# Protection_Circuit_12V.net
KiCad netlist of a schematic drawn in Altium Designer
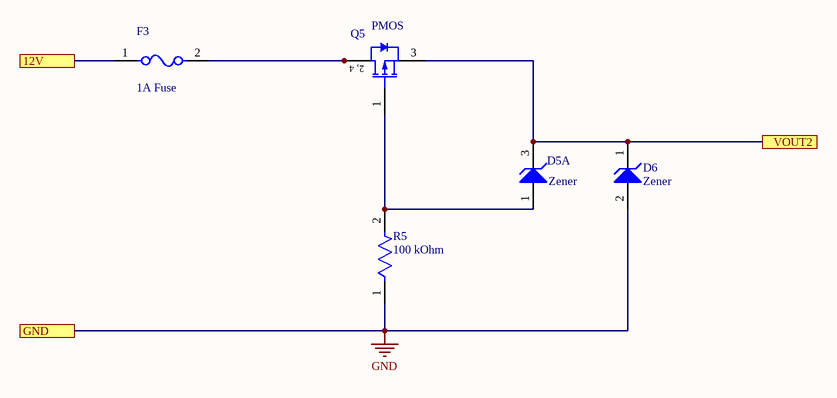
[diagram p0: Protection Circuit 12V.SchDoc]

(export (version "E")
  (design (tool "Eeschema 10.0.6"))
  (components
    (comp (ref "D5")
      (value "Zener")
      (footprint "ONSC-SOT-23-3-318-08_V")
      (description "Zener Voltage Regulator, 225 mW, 3-Pin SOT-23, Pb-Free, Tape and Reel")
      (fields (field (name "PARTNUMBER") "MMBZ5245BLT3G") (field (name "MANUFACTURER") "On Semiconductor"))
      (libsource (lib "Altium Content Vault") (part "ONSC-A1K3-3"))
    )
    (comp (ref "D6")
      (value "Zener")
      (footprint "ONSC-SMB-2-403A-03_H_V")
      (description "3 W Zener Voltage Regulator, 2-Pin SMB, Pb-Free, Tape and Reel")
      (fields (field (name "MANUFACTURER") "On Semiconductor") (field (name "PARTNUMBER") "1SMB5927BT3G"))
      (libsource (lib "Altium Content Vault") (part "ONSC-K1A2-2"))
    )
    (comp (ref "F3")
      (value "1A Fuse")
      (footprint "FP-0603SFS-MFG")
      (description "FUSE BOARD MOUNT 1A 32VDC 0603")
      (fields
        (field (name "OCTOPART") "https://octopart.com/0603sfs100f%2F32-2-littelfuse-74214378")
        (field (name "MANUFACTURER PART NUMBER") "0603SFS100F/32-2")
      )
      (libsource (lib "Altium Content Vault") (part "5bcf9b9f640e542cf0359d10258e979"))
    )
    (comp (ref "Q5")
      (value "PMOS")
      (footprint "FAIR-SOT223-4_V")
      (fields (field (name "MANUFACTURER") "Fairchild Semiconductor"))
      (libsource (lib "Altium Content Vault") (part "PEMOS-GDSD-4"))
    )
    (comp (ref "R5")
      (value "100 kOhm")
      (footprint "FP-CR0805-MFG")
      (description "Thick Film Chip Resistors 0805 100kΩ 0.125W 5% 200ppm/°C")
      (fields (field (name "TOLERANCE") "5%"))
      (libsource (lib "Altium Content Vault") (part "1029c3af85768c4190bb7ad29bc67b5"))
    )
  )
  (nets
    (net (code "1") (name "/12V") (class "Default")
      (node (ref "F3") (pin "1") (pinfunction "1_1") (pintype "passive"))
    )
    (net (code "2") (name "/VOUT2") (class "Default")
      (node (ref "D5") (pin "3") (pinfunction "K_3") (pintype "passive"))
      (node (ref "D6") (pin "1") (pinfunction "K_1") (pintype "passive"))
      (node (ref "Q5") (pin "3") (pinfunction "SOURCE_3") (pintype "passive"))
    )
    (net (code "3") (name "GND") (class "Default")
      (node (ref "D6") (pin "2") (pinfunction "A_2") (pintype "passive"))
      (node (ref "R5") (pin "1") (pinfunction "1_1") (pintype "passive"))
    )
    (net (code "4") (name "Net-(D5A-A)") (class "Default")
      (node (ref "D5") (pin "1") (pinfunction "A_1") (pintype "passive"))
      (node (ref "Q5") (pin "1") (pinfunction "GATE_1") (pintype "passive"))
      (node (ref "R5") (pin "2") (pinfunction "2_2") (pintype "passive"))
    )
    (net (code "5") (name "Net-(F3-Pad2)") (class "Default")
      (node (ref "F3") (pin "2") (pinfunction "2_2") (pintype "passive"))
      (node (ref "Q5") (pin "2") (pinfunction "DRAIN_2") (pintype "passive"))
      (node (ref "Q5") (pin "4") (pinfunction "DRAIN_4") (pintype "passive"))
    )
  )
)
